# V2_USB-GL850A.net
KiCad netlist of a schematic drawn in Altium Designer
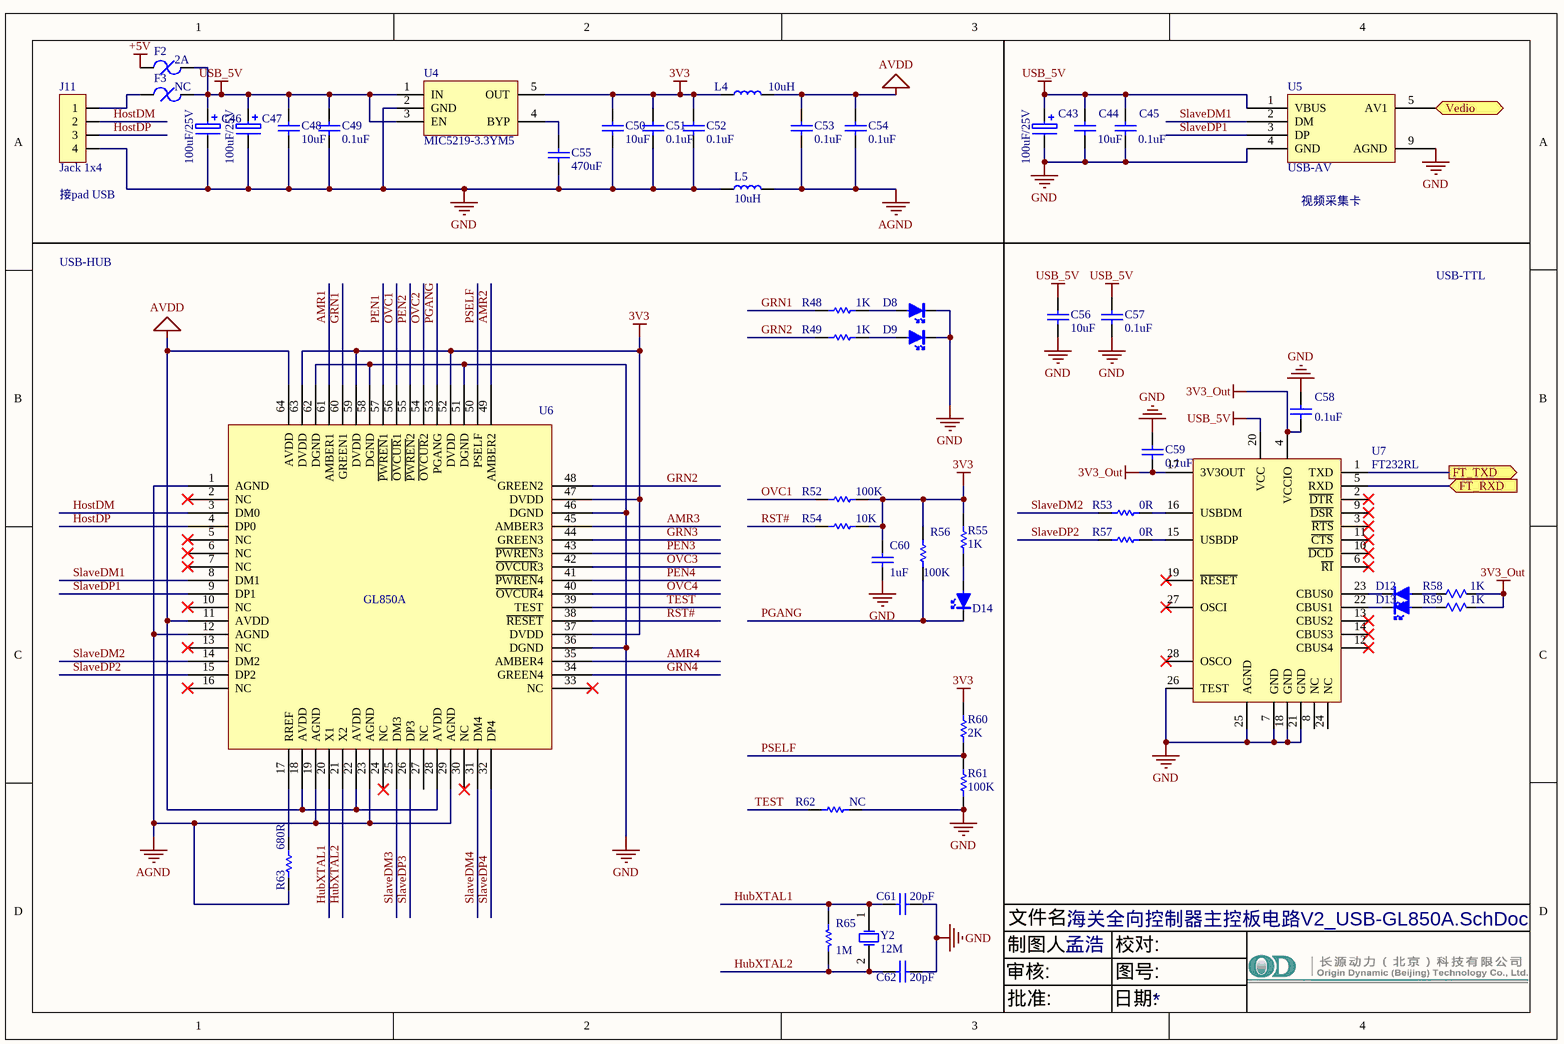
[diagram p0: 海关全向控制器主控板电路V2_USB-GL850A.SchDoc]

(export (version "E")
  (design (tool "Eeschema 10.0.6"))
  (components
    (comp (ref "C43") (value "100uF/25V") (footprint "C7343") (libsource (lib "RLCYDF") (part "Cap Poll")))
    (comp (ref "C44")
      (value "10uF")
      (footprint "C0603")
      (description "CAP")
      (fields (field (name "PUBLISHER") "Altium Limited"))
      (libsource (lib "Passive Components Class") (part "CAP"))
    )
    (comp (ref "C45") (value "0.1uF") (footprint "C0603") (libsource (lib "SMD") (part "Cap Semi")))
    (comp (ref "C46") (value "100uF/25V") (footprint "C7343") (libsource (lib "RLCYDF") (part "Cap Poll")))
    (comp (ref "C47") (value "100uF/25V") (footprint "C7343") (libsource (lib "RLCYDF") (part "Cap Poll")))
    (comp (ref "C48")
      (value "10uF")
      (footprint "C0603")
      (description "CAP")
      (fields (field (name "PUBLISHER") "Altium Limited"))
      (libsource (lib "Passive Components Class") (part "CAP"))
    )
    (comp (ref "C49") (value "0.1uF") (footprint "C0603") (libsource (lib "SMD") (part "Cap Semi")))
    (comp (ref "C50")
      (value "10uF")
      (footprint "C0603")
      (description "CAP")
      (fields (field (name "PUBLISHER") "Altium Limited"))
      (libsource (lib "Passive Components Class") (part "CAP"))
    )
    (comp (ref "C51") (value "0.1uF") (footprint "C0603") (libsource (lib "SMD") (part "Cap Semi")))
    (comp (ref "C52") (value "0.1uF") (footprint "C0603") (libsource (lib "SMD") (part "Cap Semi")))
    (comp (ref "C53") (value "0.1uF") (footprint "C0603") (libsource (lib "SMD") (part "Cap Semi")))
    (comp (ref "C54") (value "0.1uF") (footprint "C0603") (libsource (lib "SMD") (part "Cap Semi")))
    (comp (ref "C55") (value "470uF") (footprint "C0603") (libsource (lib "SMD") (part "Cap Semi")))
    (comp (ref "C56")
      (value "10uF")
      (footprint "C0603")
      (description "CAP")
      (fields (field (name "PUBLISHER") "Altium Limited"))
      (libsource (lib "Passive Components Class") (part "CAP"))
    )
    (comp (ref "C57") (value "0.1uF") (footprint "C0603") (libsource (lib "SMD") (part "Cap Semi")))
    (comp (ref "C58")
      (value "0.1uF")
      (footprint "C0603")
      (description "Capacitor")
      (fields (field (name "PUBLISHER") "Altium Limited"))
      (libsource (lib "Miscellaneous Devices") (part "Cap"))
    )
    (comp (ref "C59") (value "0.1uF") (footprint "C0603") (libsource (lib "SMD") (part "Cap Semi")))
    (comp (ref "C60") (value "1uF") (footprint "C0603") (libsource (lib "SMD") (part "Cap Semi")))
    (comp (ref "C61") (value "20pF") (footprint "C0603") (libsource (lib "SMD") (part "Cap Semi")))
    (comp (ref "C62") (value "20pF") (footprint "C0603") (libsource (lib "SMD") (part "Cap Semi")))
    (comp (ref "D8")
      (value "LED")
      (footprint "LED0603")
      (libsource (lib "Passive Components Class") (part "LED"))
    )
    (comp (ref "D9")
      (value "LED")
      (footprint "LED0603")
      (libsource (lib "Passive Components Class") (part "LED"))
    )
    (comp (ref "D12")
      (value "LED")
      (footprint "LED0603")
      (libsource (lib "Passive Components Class") (part "LED"))
    )
    (comp (ref "D13")
      (value "LED")
      (footprint "LED0603")
      (libsource (lib "Passive Components Class") (part "LED"))
    )
    (comp (ref "D14")
      (value "LED")
      (footprint "LED0603")
      (libsource (lib "Passive Components Class") (part "LED"))
    )
    (comp (ref "F2") (value "2A") (footprint "F1218") (libsource (lib "RLCYDF") (part "Fuse2")))
    (comp (ref "F3") (value "NC") (footprint "F1218") (libsource (lib "RLCYDF") (part "Fuse2")))
    (comp (ref "J11")
      (value "Jack 1x4")
      (footprint "ZH1.5-4AWD")
      (description "插座")
      (libsource (lib "Connector") (part "Jack 1x4"))
    )
    (comp (ref "L4") (value "10uH") (footprint "L0805") (libsource (lib "RLCYDF") (part "Inductor")))
    (comp (ref "L5") (value "10uH") (footprint "L0805") (libsource (lib "RLCYDF") (part "Inductor")))
    (comp (ref "R48") (value "1K") (footprint "R0603") (libsource (lib "SMD") (part "Res")))
    (comp (ref "R49") (value "1K") (footprint "R0603") (libsource (lib "SMD") (part "Res")))
    (comp (ref "R52") (value "100K") (footprint "R0603") (libsource (lib "SMD") (part "Res")))
    (comp (ref "R53") (value "0R") (footprint "R0603") (libsource (lib "SMD") (part "Res")))
    (comp (ref "R54") (value "10K") (footprint "R0603") (libsource (lib "SMD") (part "Res")))
    (comp (ref "R55") (value "1K") (footprint "R0603") (libsource (lib "SMD") (part "Res")))
    (comp (ref "R56") (value "100K") (footprint "R0603") (libsource (lib "SMD") (part "Res")))
    (comp (ref "R57") (value "0R") (footprint "R0603") (libsource (lib "SMD") (part "Res")))
    (comp (ref "R58")
      (value "1K")
      (footprint "R0603")
      (description "Resistor")
      (fields (field (name "PUBLISHER") "Altium Limited"))
      (libsource (lib "Temp") (part "Res"))
    )
    (comp (ref "R59")
      (value "1K")
      (footprint "R0603")
      (description "Resistor")
      (fields (field (name "PUBLISHER") "Altium Limited"))
      (libsource (lib "Temp") (part "Res"))
    )
    (comp (ref "R60") (value "2K") (footprint "R0603") (libsource (lib "SMD") (part "Res")))
    (comp (ref "R61") (value "100K") (footprint "R0603") (libsource (lib "SMD") (part "Res")))
    (comp (ref "R62") (value "NC") (footprint "R0603") (libsource (lib "SMD") (part "Res")))
    (comp (ref "R63") (value "680R") (footprint "R0603") (libsource (lib "SMD") (part "Res")))
    (comp (ref "R65") (value "1M") (footprint "R0603") (libsource (lib "SMD") (part "Res")))
    (comp (ref "U4")
      (value "MIC5219-3.3YM5")
      (footprint "SOT-23-5")
      (libsource (lib "Power") (part "MIC5205"))
    )
    (comp (ref "U5") (value "USB-AV") (footprint "USB-AV") (libsource (lib "Module") (part "USB-AV")))
    (comp (ref "U6") (value "GL850A") (footprint "LQF64") (libsource (lib "chip") (part "GL850A")))
    (comp (ref "U7")
      (value "FT232RL")
      (footprint "SSOP-28")
      (libsource (lib "海关全向控制器主控板V2") (part "FT232RL"))
    )
    (comp (ref "Y2")
      (value "12M")
      (footprint "HC49S")
      (description "Crystal Oscillator")
      (fields (field (name "PUBLISHER") "Altium Limited"))
      (libsource (lib "Miscellaneous Devices") (part "XTAL"))
    )
  )
  (nets
    (net (code "1") (name "+5V") (class "Default")
      (node (ref "F2") (pin "1") (pinfunction "1_1") (pintype "passive"))
    )
    (net (code "2") (name "/AMR1") (class "Default")
      (node (ref "U6") (pin "61") (pinfunction "AMBER1_61") (pintype "passive"))
    )
    (net (code "3") (name "/AMR2") (class "Default")
      (node (ref "U6") (pin "49") (pinfunction "AMBER2_49") (pintype "passive"))
    )
    (net (code "4") (name "/AMR3") (class "Default")
      (node (ref "U6") (pin "45") (pinfunction "AMBER3_45") (pintype "passive"))
    )
    (net (code "5") (name "/AMR4") (class "Default")
      (node (ref "U6") (pin "35") (pinfunction "AMBER4_35") (pintype "passive"))
    )
    (net (code "6") (name "/FT_RXD") (class "Default")
      (node (ref "U7") (pin "5") (pinfunction "RXD_5") (pintype "passive"))
    )
    (net (code "7") (name "/FT_TXD") (class "Default")
      (node (ref "U7") (pin "1") (pinfunction "TXD_1") (pintype "passive"))
    )
    (net (code "8") (name "/GRN1") (class "Default")
      (node (ref "R48") (pin "1") (pinfunction "1_1") (pintype "passive"))
      (node (ref "U6") (pin "60") (pinfunction "GREEN1_60") (pintype "passive"))
    )
    (net (code "9") (name "/GRN2") (class "Default")
      (node (ref "R49") (pin "1") (pinfunction "1_1") (pintype "passive"))
      (node (ref "U6") (pin "48") (pinfunction "GREEN2_48") (pintype "passive"))
    )
    (net (code "10") (name "/GRN3") (class "Default")
      (node (ref "U6") (pin "44") (pinfunction "GREEN3_44") (pintype "passive"))
    )
    (net (code "11") (name "/GRN4") (class "Default")
      (node (ref "U6") (pin "34") (pinfunction "GREEN4_34") (pintype "passive"))
    )
    (net (code "12") (name "/HostDM") (class "Default")
      (node (ref "J11") (pin "2") (pinfunction "2_2") (pintype "passive"))
      (node (ref "U6") (pin "3") (pinfunction "DM0_3") (pintype "passive"))
    )
    (net (code "13") (name "/HostDP") (class "Default")
      (node (ref "J11") (pin "3") (pinfunction "3_3") (pintype "passive"))
      (node (ref "U6") (pin "4") (pinfunction "DP0_4") (pintype "passive"))
    )
    (net (code "14") (name "/HubXTAL1") (class "Default")
      (node (ref "C61") (pin "1") (pinfunction "1_1") (pintype "passive"))
      (node (ref "R65") (pin "2") (pinfunction "2_2") (pintype "passive"))
      (node (ref "U6") (pin "20") (pinfunction "X1_20") (pintype "passive"))
      (node (ref "Y2") (pin "1") (pinfunction "OSC1_1") (pintype "passive"))
    )
    (net (code "15") (name "/HubXTAL2") (class "Default")
      (node (ref "C62") (pin "1") (pinfunction "1_1") (pintype "passive"))
      (node (ref "R65") (pin "1") (pinfunction "1_1") (pintype "passive"))
      (node (ref "U6") (pin "21") (pinfunction "X2_21") (pintype "passive"))
      (node (ref "Y2") (pin "2") (pinfunction "OSC2_2") (pintype "passive"))
    )
    (net (code "16") (name "/OVC1") (class "Default")
      (node (ref "R52") (pin "1") (pinfunction "1_1") (pintype "passive"))
      (node (ref "U6") (pin "56") (pinfunction "~{OVCUR}1_56") (pintype "passive"))
    )
    (net (code "17") (name "/OVC2") (class "Default")
      (node (ref "U6") (pin "54") (pinfunction "~{OVCUR}2_54") (pintype "passive"))
    )
    (net (code "18") (name "/OVC3") (class "Default")
      (node (ref "U6") (pin "42") (pinfunction "~{OVCUR}3_42") (pintype "passive"))
    )
    (net (code "19") (name "/OVC4") (class "Default")
      (node (ref "U6") (pin "40") (pinfunction "~{OVCUR}4_40") (pintype "passive"))
    )
    (net (code "20") (name "/PEN1") (class "Default")
      (node (ref "U6") (pin "57") (pinfunction "~{PWREN}1_57") (pintype "passive"))
    )
    (net (code "21") (name "/PEN2") (class "Default")
      (node (ref "U6") (pin "55") (pinfunction "~{PWREN}2_55") (pintype "passive"))
    )
    (net (code "22") (name "/PEN3") (class "Default")
      (node (ref "U6") (pin "43") (pinfunction "~{PWREN}3_43") (pintype "passive"))
    )
    (net (code "23") (name "/PEN4") (class "Default")
      (node (ref "U6") (pin "41") (pinfunction "~{PWREN}4_41") (pintype "passive"))
    )
    (net (code "24") (name "/PGANG") (class "Default")
      (node (ref "D14") (pin "2") (pinfunction "K_2") (pintype "passive"))
      (node (ref "R56") (pin "1") (pinfunction "1_1") (pintype "passive"))
      (node (ref "U6") (pin "53") (pinfunction "PGANG_53") (pintype "passive"))
    )
    (net (code "25") (name "/PSELF") (class "Default")
      (node (ref "R60") (pin "1") (pinfunction "1_1") (pintype "passive"))
      (node (ref "R61") (pin "2") (pinfunction "2_2") (pintype "passive"))
      (node (ref "U6") (pin "50") (pinfunction "PSELF_50") (pintype "passive"))
    )
    (net (code "26") (name "/RST#") (class "Default")
      (node (ref "R54") (pin "1") (pinfunction "1_1") (pintype "passive"))
      (node (ref "U6") (pin "38") (pinfunction "~{RESET}_38") (pintype "passive"))
    )
    (net (code "27") (name "/SlaveDM1") (class "Default")
      (node (ref "U5") (pin "2") (pinfunction "DM_2") (pintype "passive"))
      (node (ref "U6") (pin "8") (pinfunction "DM1_8") (pintype "passive"))
    )
    (net (code "28") (name "/SlaveDM2") (class "Default")
      (node (ref "R53") (pin "1") (pinfunction "1_1") (pintype "passive"))
      (node (ref "U6") (pin "14") (pinfunction "DM2_14") (pintype "passive"))
    )
    (net (code "29") (name "/SlaveDM3") (class "Default")
      (node (ref "U6") (pin "25") (pinfunction "DM3_25") (pintype "passive"))
    )
    (net (code "30") (name "/SlaveDM4") (class "Default")
      (node (ref "U6") (pin "31") (pinfunction "DM4_31") (pintype "passive"))
    )
    (net (code "31") (name "/SlaveDP1") (class "Default")
      (node (ref "U5") (pin "3") (pinfunction "DP_3") (pintype "passive"))
      (node (ref "U6") (pin "9") (pinfunction "DP1_9") (pintype "passive"))
    )
    (net (code "32") (name "/SlaveDP2") (class "Default")
      (node (ref "R57") (pin "1") (pinfunction "1_1") (pintype "passive"))
      (node (ref "U6") (pin "15") (pinfunction "DP2_15") (pintype "passive"))
    )
    (net (code "33") (name "/SlaveDP3") (class "Default")
      (node (ref "U6") (pin "26") (pinfunction "DP3_26") (pintype "passive"))
    )
    (net (code "34") (name "/SlaveDP4") (class "Default")
      (node (ref "U6") (pin "32") (pinfunction "DP4_32") (pintype "passive"))
    )
    (net (code "35") (name "/TEST") (class "Default")
      (node (ref "R62") (pin "1") (pinfunction "1_1") (pintype "passive"))
      (node (ref "U6") (pin "39") (pinfunction "TEST_39") (pintype "passive"))
    )
    (net (code "36") (name "/Vedio") (class "Default")
      (node (ref "U5") (pin "5") (pinfunction "AV1_5") (pintype "passive"))
    )
    (net (code "37") (name "3V3") (class "Default")
      (node (ref "C50") (pin "1") (pinfunction "1_1") (pintype "passive"))
      (node (ref "C51") (pin "2") (pinfunction "2_2") (pintype "passive"))
      (node (ref "C52") (pin "2") (pinfunction "2_2") (pintype "passive"))
      (node (ref "C60") (pin "2") (pinfunction "2_2") (pintype "passive"))
      (node (ref "L4") (pin "1") (pinfunction "1_1") (pintype "passive"))
      (node (ref "R52") (pin "2") (pinfunction "2_2") (pintype "passive"))
      (node (ref "R54") (pin "2") (pinfunction "2_2") (pintype "passive"))
      (node (ref "R55") (pin "1") (pinfunction "1_1") (pintype "passive"))
      (node (ref "R56") (pin "2") (pinfunction "2_2") (pintype "passive"))
      (node (ref "R60") (pin "2") (pinfunction "2_2") (pintype "passive"))
      (node (ref "U4") (pin "5") (pinfunction "OUT_5") (pintype "passive"))
      (node (ref "U6") (pin "37") (pinfunction "DVDD_37") (pintype "passive"))
      (node (ref "U6") (pin "47") (pinfunction "DVDD_47") (pintype "passive"))
      (node (ref "U6") (pin "52") (pinfunction "DVDD_52") (pintype "passive"))
      (node (ref "U6") (pin "59") (pinfunction "DVDD_59") (pintype "passive"))
      (node (ref "U6") (pin "63") (pinfunction "DVDD_63") (pintype "passive"))
    )
    (net (code "38") (name "3V3_Out") (class "Default")
      (node (ref "C58") (pin "2") (pinfunction "2_2") (pintype "passive"))
      (node (ref "C59") (pin "1") (pinfunction "1_1") (pintype "passive"))
      (node (ref "R58") (pin "1") (pinfunction "1_1") (pintype "passive"))
      (node (ref "R59") (pin "1") (pinfunction "1_1") (pintype "passive"))
      (node (ref "U7") (pin "17") (pinfunction "3V3OUT_17") (pintype "passive"))
      (node (ref "U7") (pin "4") (pinfunction "VCCIO_4") (pintype "passive"))
    )
    (net (code "39") (name "AGND") (class "Default")
      (node (ref "C53") (pin "1") (pinfunction "1_1") (pintype "passive"))
      (node (ref "C54") (pin "1") (pinfunction "1_1") (pintype "passive"))
      (node (ref "L5") (pin "2") (pinfunction "2_2") (pintype "passive"))
      (node (ref "R63") (pin "1") (pinfunction "1_1") (pintype "passive"))
      (node (ref "U6") (pin "1") (pinfunction "AGND_1") (pintype "passive"))
      (node (ref "U6") (pin "12") (pinfunction "AGND_12") (pintype "passive"))
      (node (ref "U6") (pin "19") (pinfunction "AGND_19") (pintype "passive"))
      (node (ref "U6") (pin "23") (pinfunction "AGND_23") (pintype "passive"))
      (node (ref "U6") (pin "29") (pinfunction "AGND_29") (pintype "passive"))
    )
    (net (code "40") (name "AVDD") (class "Default")
      (node (ref "C53") (pin "2") (pinfunction "2_2") (pintype "passive"))
      (node (ref "C54") (pin "2") (pinfunction "2_2") (pintype "passive"))
      (node (ref "L4") (pin "2") (pinfunction "2_2") (pintype "passive"))
      (node (ref "U6") (pin "11") (pinfunction "AVDD_11") (pintype "passive"))
      (node (ref "U6") (pin "18") (pinfunction "AVDD_18") (pintype "passive"))
      (node (ref "U6") (pin "22") (pinfunction "AVDD_22") (pintype "passive"))
      (node (ref "U6") (pin "28") (pinfunction "AVDD_28") (pintype "passive"))
      (node (ref "U6") (pin "64") (pinfunction "AVDD_64") (pintype "passive"))
    )
    (net (code "41") (name "GND") (class "Default")
      (node (ref "C43") (pin "2") (pinfunction "2_2") (pintype "passive"))
      (node (ref "C44") (pin "2") (pinfunction "2_2") (pintype "passive"))
      (node (ref "C45") (pin "1") (pinfunction "1_1") (pintype "passive"))
      (node (ref "C46") (pin "2") (pinfunction "2_2") (pintype "passive"))
      (node (ref "C47") (pin "2") (pinfunction "2_2") (pintype "passive"))
      (node (ref "C48") (pin "2") (pinfunction "2_2") (pintype "passive"))
      (node (ref "C49") (pin "1") (pinfunction "1_1") (pintype "passive"))
      (node (ref "C50") (pin "2") (pinfunction "2_2") (pintype "passive"))
      (node (ref "C51") (pin "1") (pinfunction "1_1") (pintype "passive"))
      (node (ref "C52") (pin "1") (pinfunction "1_1") (pintype "passive"))
      (node (ref "C55") (pin "1") (pinfunction "1_1") (pintype "passive"))
      (node (ref "C56") (pin "2") (pinfunction "2_2") (pintype "passive"))
      (node (ref "C57") (pin "1") (pinfunction "1_1") (pintype "passive"))
      (node (ref "C58") (pin "1") (pinfunction "1_1") (pintype "passive"))
      (node (ref "C59") (pin "2") (pinfunction "2_2") (pintype "passive"))
      (node (ref "C60") (pin "1") (pinfunction "1_1") (pintype "passive"))
      (node (ref "C61") (pin "2") (pinfunction "2_2") (pintype "passive"))
      (node (ref "C62") (pin "2") (pinfunction "2_2") (pintype "passive"))
      (node (ref "D8") (pin "2") (pinfunction "K_2") (pintype "passive"))
      (node (ref "D9") (pin "2") (pinfunction "K_2") (pintype "passive"))
      (node (ref "J11") (pin "4") (pinfunction "4_4") (pintype "passive"))
      (node (ref "L5") (pin "1") (pinfunction "1_1") (pintype "passive"))
      (node (ref "R61") (pin "1") (pinfunction "1_1") (pintype "passive"))
      (node (ref "R62") (pin "2") (pinfunction "2_2") (pintype "passive"))
      (node (ref "U4") (pin "2") (pinfunction "GND_2") (pintype "passive"))
      (node (ref "U5") (pin "4") (pinfunction "GND_4") (pintype "passive"))
      (node (ref "U5") (pin "9") (pinfunction "AGND_9") (pintype "passive"))
      (node (ref "U6") (pin "36") (pinfunction "DGND_36") (pintype "passive"))
      (node (ref "U6") (pin "46") (pinfunction "DGND_46") (pintype "passive"))
      (node (ref "U6") (pin "51") (pinfunction "DGND_51") (pintype "passive"))
      (node (ref "U6") (pin "58") (pinfunction "DGND_58") (pintype "passive"))
      (node (ref "U6") (pin "62") (pinfunction "DGND_62") (pintype "passive"))
      (node (ref "U7") (pin "18") (pinfunction "GND_18") (pintype "passive"))
      (node (ref "U7") (pin "21") (pinfunction "GND_21") (pintype "passive"))
      (node (ref "U7") (pin "25") (pinfunction "AGND_25") (pintype "passive"))
      (node (ref "U7") (pin "26") (pinfunction "TEST_26") (pintype "passive"))
      (node (ref "U7") (pin "7") (pinfunction "GND_7") (pintype "passive"))
    )
    (net (code "42") (name "Net-(D8-A)") (class "Default")
      (node (ref "D8") (pin "1") (pinfunction "A_1") (pintype "passive"))
      (node (ref "R48") (pin "2") (pinfunction "2_2") (pintype "passive"))
    )
    (net (code "43") (name "Net-(D9-A)") (class "Default")
      (node (ref "D9") (pin "1") (pinfunction "A_1") (pintype "passive"))
      (node (ref "R49") (pin "2") (pinfunction "2_2") (pintype "passive"))
    )
    (net (code "44") (name "Net-(D12-A)") (class "Default")
      (node (ref "D12") (pin "1") (pinfunction "A_1") (pintype "passive"))
      (node (ref "R58") (pin "2") (pinfunction "2_2") (pintype "passive"))
    )
    (net (code "45") (name "Net-(D12-K)") (class "Default")
      (node (ref "D12") (pin "2") (pinfunction "K_2") (pintype "passive"))
      (node (ref "U7") (pin "23") (pinfunction "CBUS0_23") (pintype "passive"))
    )
    (net (code "46") (name "Net-(D13-A)") (class "Default")
      (node (ref "D13") (pin "1") (pinfunction "A_1") (pintype "passive"))
      (node (ref "R59") (pin "2") (pinfunction "2_2") (pintype "passive"))
    )
    (net (code "47") (name "Net-(D13-K)") (class "Default")
      (node (ref "D13") (pin "2") (pinfunction "K_2") (pintype "passive"))
      (node (ref "U7") (pin "22") (pinfunction "CBUS1_22") (pintype "passive"))
    )
    (net (code "48") (name "Net-(D14-A)") (class "Default")
      (node (ref "D14") (pin "1") (pinfunction "A_1") (pintype "passive"))
      (node (ref "R55") (pin "2") (pinfunction "2_2") (pintype "passive"))
    )
    (net (code "49") (name "Net-(F3-Pad1)") (class "Default")
      (node (ref "F3") (pin "1") (pinfunction "1_1") (pintype "passive"))
      (node (ref "J11") (pin "1") (pinfunction "1_1") (pintype "passive"))
    )
    (net (code "50") (name "Net-(U4-BYP)") (class "Default")
      (node (ref "C55") (pin "2") (pinfunction "2_2") (pintype "passive"))
      (node (ref "U4") (pin "4") (pinfunction "BYP_4") (pintype "passive"))
    )
    (net (code "51") (name "Net-(U6-RREF)") (class "Default")
      (node (ref "R63") (pin "2") (pinfunction "2_2") (pintype "passive"))
      (node (ref "U6") (pin "17") (pinfunction "RREF_17") (pintype "passive"))
    )
    (net (code "52") (name "Net-(U7-USBDM)") (class "Default")
      (node (ref "R53") (pin "2") (pinfunction "2_2") (pintype "passive"))
      (node (ref "U7") (pin "16") (pinfunction "USBDM_16") (pintype "passive"))
    )
    (net (code "53") (name "Net-(U7-USBDP)") (class "Default")
      (node (ref "R57") (pin "2") (pinfunction "2_2") (pintype "passive"))
      (node (ref "U7") (pin "15") (pinfunction "USBDP_15") (pintype "passive"))
    )
    (net (code "54") (name "USB_5V") (class "Default")
      (node (ref "C43") (pin "1") (pinfunction "1_1") (pintype "passive"))
      (node (ref "C44") (pin "1") (pinfunction "1_1") (pintype "passive"))
      (node (ref "C45") (pin "2") (pinfunction "2_2") (pintype "passive"))
      (node (ref "C46") (pin "1") (pinfunction "1_1") (pintype "passive"))
      (node (ref "C47") (pin "1") (pinfunction "1_1") (pintype "passive"))
      (node (ref "C48") (pin "1") (pinfunction "1_1") (pintype "passive"))
      (node (ref "C49") (pin "2") (pinfunction "2_2") (pintype "passive"))
      (node (ref "C56") (pin "1") (pinfunction "1_1") (pintype "passive"))
      (node (ref "C57") (pin "2") (pinfunction "2_2") (pintype "passive"))
      (node (ref "F2") (pin "2") (pinfunction "2_2") (pintype "passive"))
      (node (ref "F3") (pin "2") (pinfunction "2_2") (pintype "passive"))
      (node (ref "U4") (pin "1") (pinfunction "IN_1") (pintype "passive"))
      (node (ref "U4") (pin "3") (pinfunction "EN_3") (pintype "passive"))
      (node (ref "U5") (pin "1") (pinfunction "VBUS_1") (pintype "passive"))
      (node (ref "U7") (pin "20") (pinfunction "VCC_20") (pintype "passive"))
    )
    (net (code "55") (name "unconnected-(U6-NC-Pad2)") (class "Default")
      (node (ref "U6") (pin "2") (pinfunction "NC_2") (pintype "passive+no_connect"))
    )
    (net (code "56") (name "unconnected-(U6-NC-Pad5)") (class "Default")
      (node (ref "U6") (pin "5") (pinfunction "NC_5") (pintype "passive+no_connect"))
    )
    (net (code "57") (name "unconnected-(U6-NC-Pad6)") (class "Default")
      (node (ref "U6") (pin "6") (pinfunction "NC_6") (pintype "passive+no_connect"))
    )
    (net (code "58") (name "unconnected-(U6-NC-Pad7)") (class "Default")
      (node (ref "U6") (pin "7") (pinfunction "NC_7") (pintype "passive+no_connect"))
    )
    (net (code "59") (name "unconnected-(U6-NC-Pad10)") (class "Default")
      (node (ref "U6") (pin "10") (pinfunction "NC_10") (pintype "passive+no_connect"))
    )
    (net (code "60") (name "unconnected-(U6-NC-Pad13)") (class "Default")
      (node (ref "U6") (pin "13") (pinfunction "NC_13") (pintype "passive+no_connect"))
    )
    (net (code "61") (name "unconnected-(U6-NC-Pad16)") (class "Default")
      (node (ref "U6") (pin "16") (pinfunction "NC_16") (pintype "passive+no_connect"))
    )
    (net (code "62") (name "unconnected-(U6-NC-Pad24)") (class "Default")
      (node (ref "U6") (pin "24") (pinfunction "NC_24") (pintype "passive+no_connect"))
    )
    (net (code "63") (name "unconnected-(U6-NC-Pad27)") (class "Default")
      (node (ref "U6") (pin "27") (pinfunction "NC_27") (pintype "passive"))
    )
    (net (code "64") (name "unconnected-(U6-NC-Pad30)") (class "Default")
      (node (ref "U6") (pin "30") (pinfunction "NC_30") (pintype "passive+no_connect"))
    )
    (net (code "65") (name "unconnected-(U6-NC-Pad33)") (class "Default")
      (node (ref "U6") (pin "33") (pinfunction "NC_33") (pintype "passive+no_connect"))
    )
    (net (code "66") (name "unconnected-(U7-CBUS2-Pad13)") (class "Default")
      (node (ref "U7") (pin "13") (pinfunction "CBUS2_13") (pintype "passive+no_connect"))
    )
    (net (code "67") (name "unconnected-(U7-CBUS3-Pad14)") (class "Default")
      (node (ref "U7") (pin "14") (pinfunction "CBUS3_14") (pintype "passive+no_connect"))
    )
    (net (code "68") (name "unconnected-(U7-CBUS4-Pad12)") (class "Default")
      (node (ref "U7") (pin "12") (pinfunction "CBUS4_12") (pintype "passive+no_connect"))
    )
    (net (code "69") (name "unconnected-(U7-NC-Pad8)") (class "Default")
      (node (ref "U7") (pin "8") (pinfunction "NC_8") (pintype "passive"))
    )
    (net (code "70") (name "unconnected-(U7-NC-Pad24)") (class "Default")
      (node (ref "U7") (pin "24") (pinfunction "NC_24") (pintype "passive"))
    )
    (net (code "71") (name "unconnected-(U7-OSCI-Pad27)") (class "Default")
      (node (ref "U7") (pin "27") (pinfunction "OSCI_27") (pintype "passive+no_connect"))
    )
    (net (code "72") (name "unconnected-(U7-OSCO-Pad28)") (class "Default")
      (node (ref "U7") (pin "28") (pinfunction "OSCO_28") (pintype "passive+no_connect"))
    )
    (net (code "73") (name "unconnected-(U7-~{CTS}-Pad11)") (class "Default")
      (node (ref "U7") (pin "11") (pinfunction "~{CTS}_11") (pintype "passive+no_connect"))
    )
    (net (code "74") (name "unconnected-(U7-~{DCD}-Pad10)") (class "Default")
      (node (ref "U7") (pin "10") (pinfunction "~{DCD}_10") (pintype "passive+no_connect"))
    )
    (net (code "75") (name "unconnected-(U7-~{DSR}-Pad9)") (class "Default")
      (node (ref "U7") (pin "9") (pinfunction "~{DSR}_9") (pintype "passive+no_connect"))
    )
    (net (code "76") (name "unconnected-(U7-~{DTR}-Pad2)") (class "Default")
      (node (ref "U7") (pin "2") (pinfunction "~{DTR}_2") (pintype "passive+no_connect"))
    )
    (net (code "77") (name "unconnected-(U7-~{RESET}-Pad19)") (class "Default")
      (node (ref "U7") (pin "19") (pinfunction "~{RESET}_19") (pintype "passive+no_connect"))
    )
    (net (code "78") (name "unconnected-(U7-~{RI}-Pad6)") (class "Default")
      (node (ref "U7") (pin "6") (pinfunction "~{RI}_6") (pintype "passive+no_connect"))
    )
    (net (code "79") (name "unconnected-(U7-~{RTS}-Pad3)") (class "Default")
      (node (ref "U7") (pin "3") (pinfunction "~{RTS}_3") (pintype "passive+no_connect"))
    )
  )
)
